# PM.net
KiCad netlist of a schematic drawn in Altium Designer
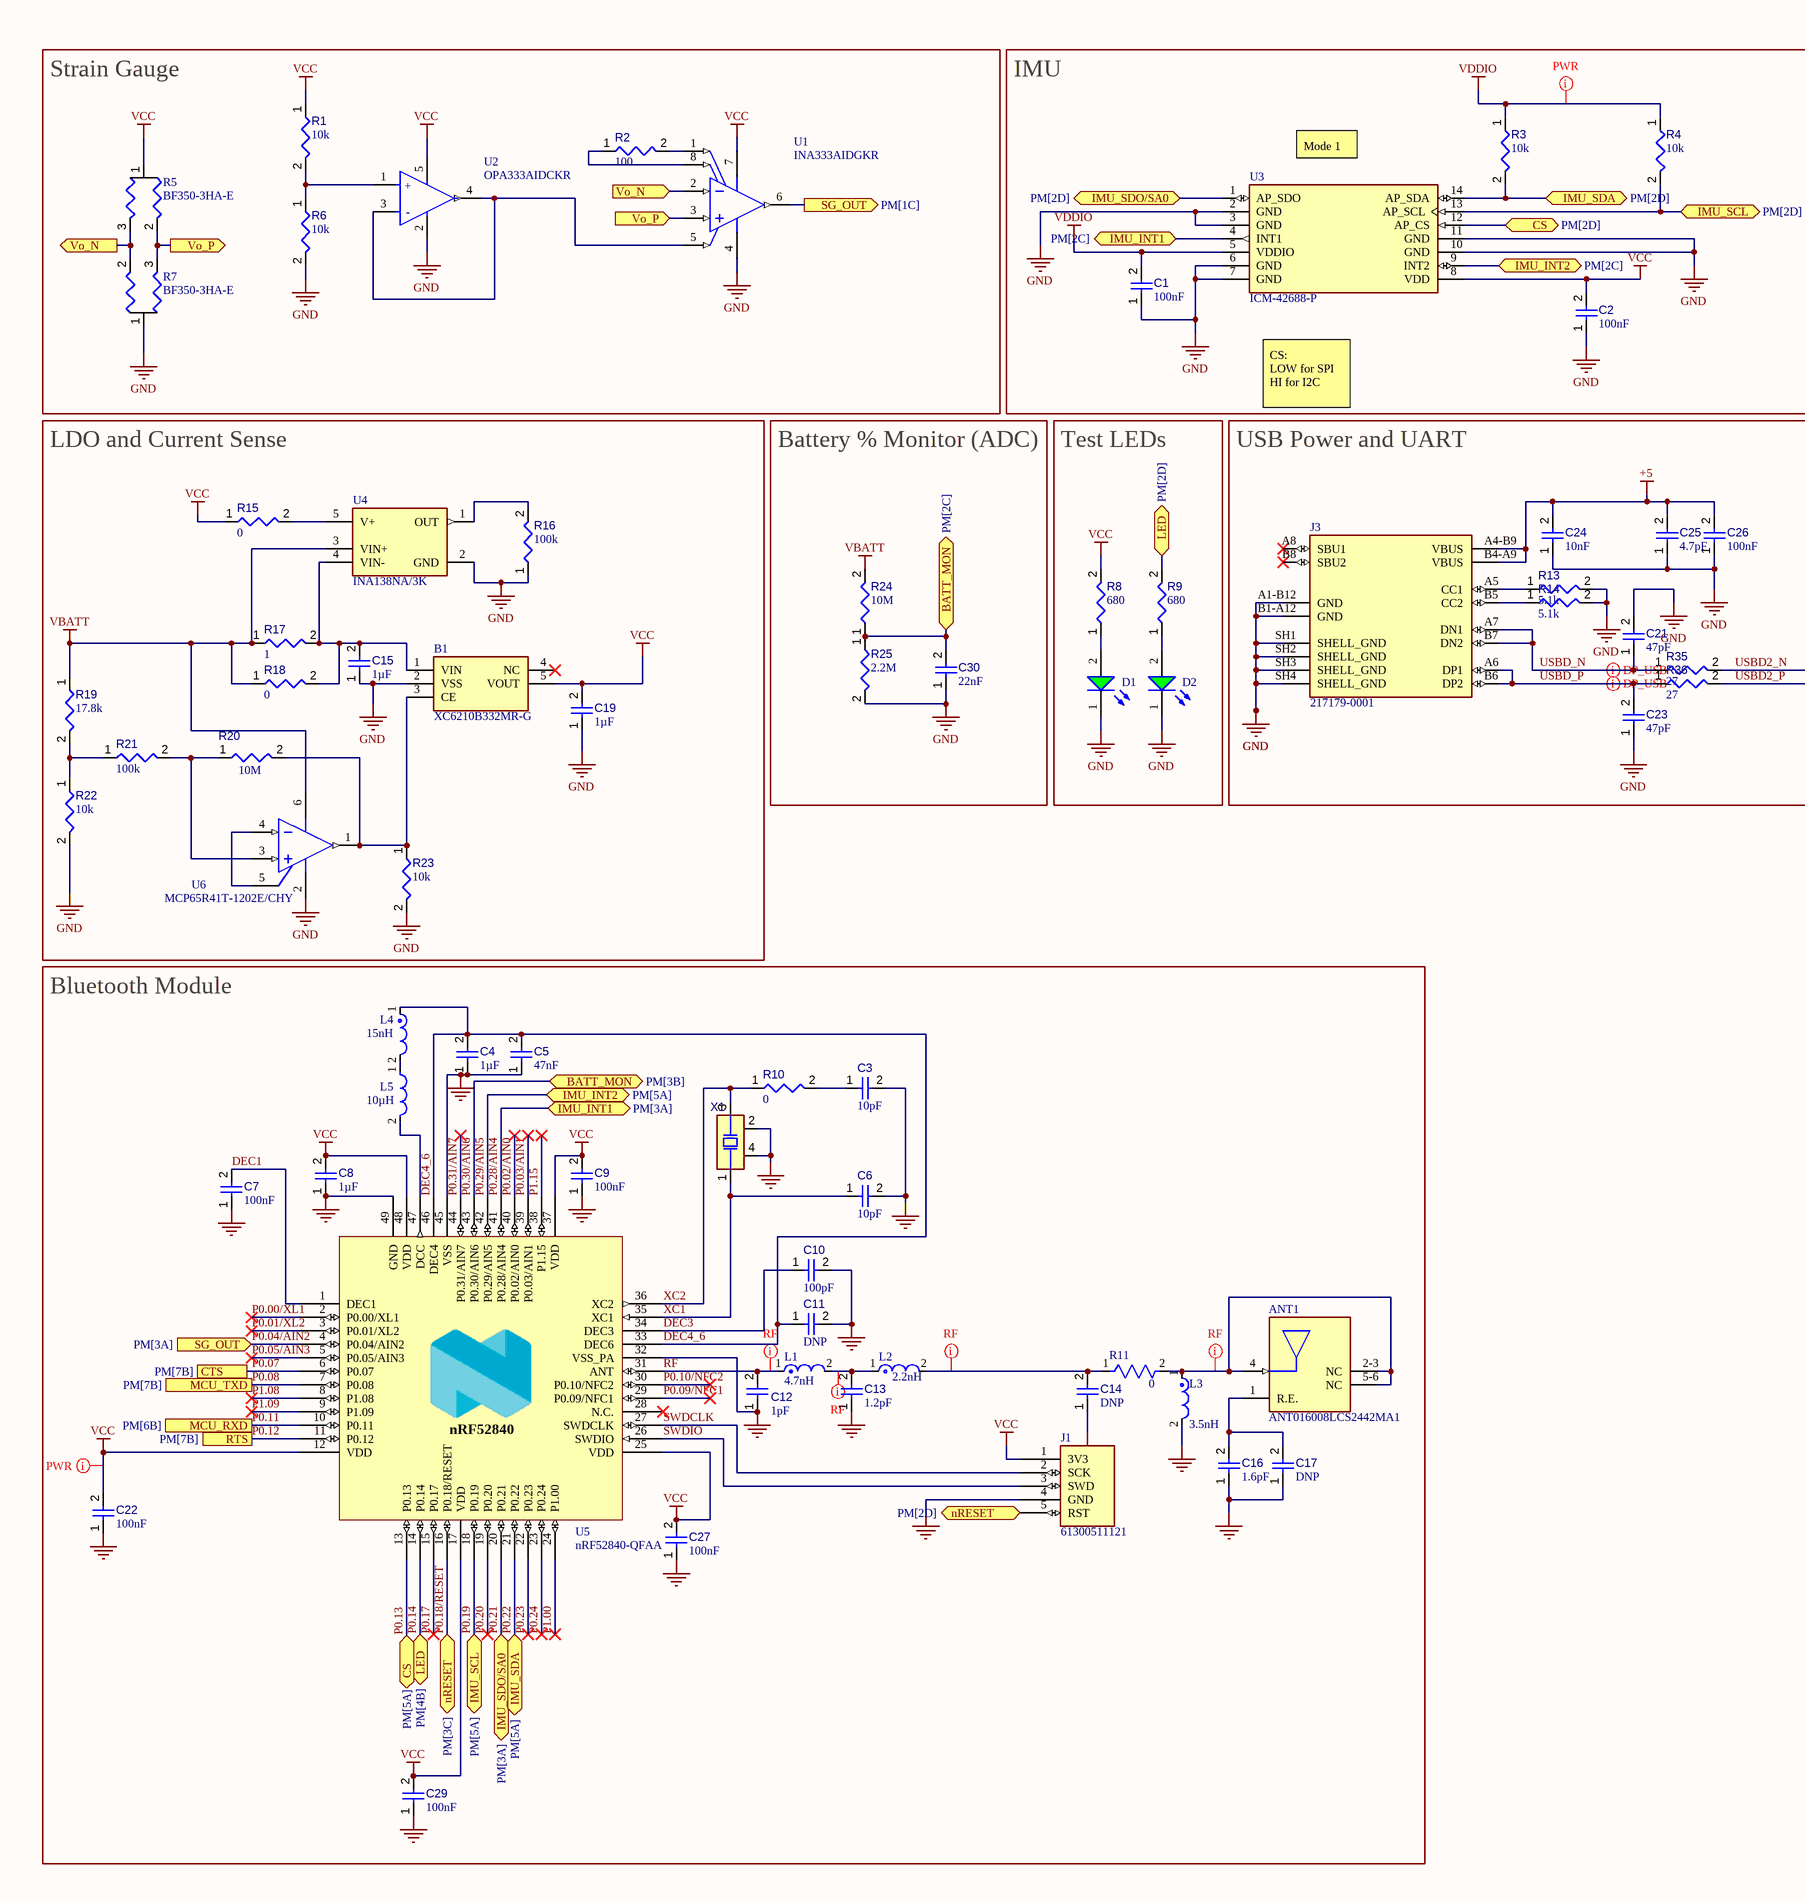
[diagram p0: PM.SchDoc, left]
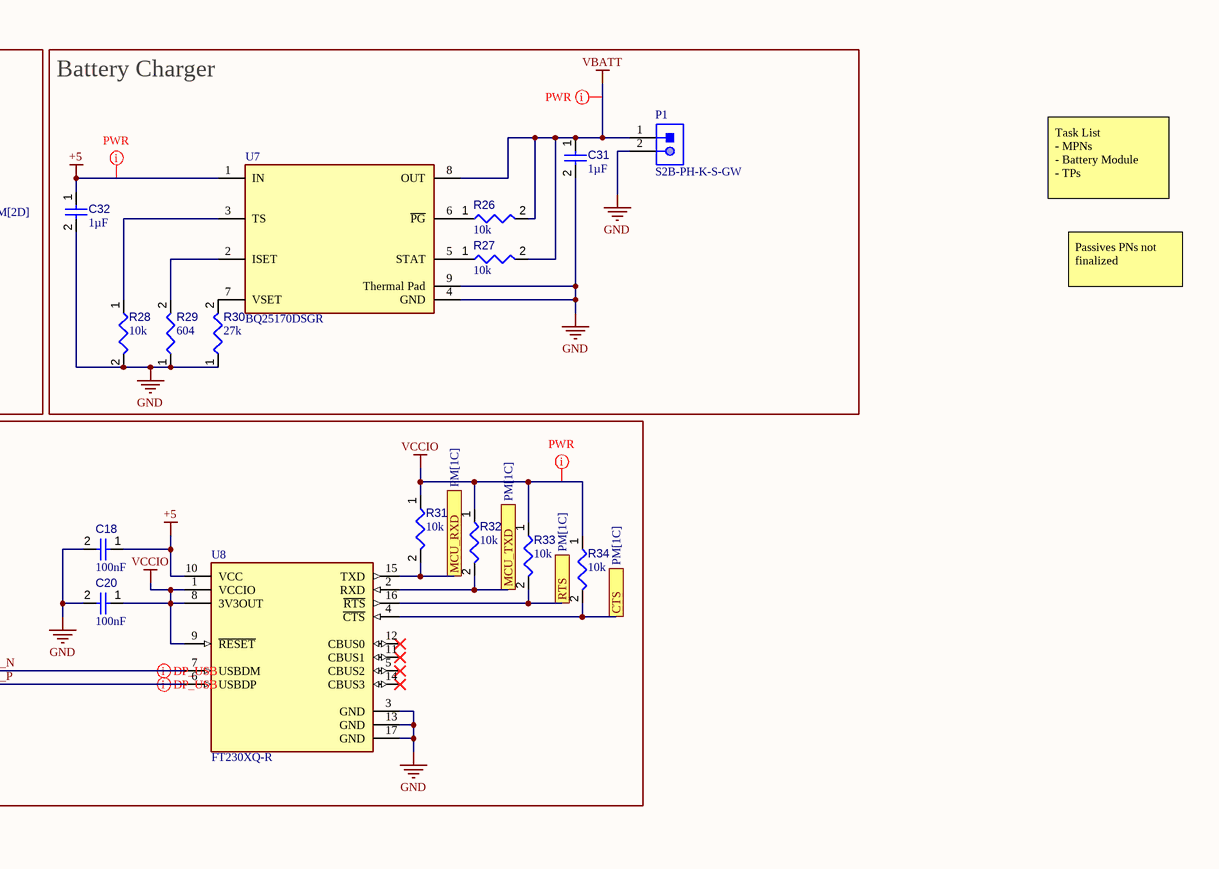
[diagram p1: PM.SchDoc, right]

(export (version "E")
  (design (tool "Eeschema 10.0.6"))
  (components
    (comp (ref "ANT1")
      (value "ANT016008LCS2442MA1")
      (footprint "FP-ANT016-MFG")
      (description "RF/Microwave Antenna, 2400MHz Min, 2484MHz Max")
      (libsource (lib "Capstone") (part "f1d90557cadd8a372defdcae6904fa8"))
    )
    (comp (ref "B1")
      (value "XC6210B332MR-G")
      (footprint "SOT95P280X130-5N")
      (description "LDO Voltage Regulators 700mA High Speed Votage Regulator")
      (fields (field (name "MOUSER PART NUMBER") "865-XC6210B332MR-G"))
      (libsource (lib "Capstone") (part "XC6210B332MR-G"))
    )
    (comp (ref "C1")
      (value "100nF")
      (footprint "FP-GRM15-IPC_B")
      (fields (field (name "Comment") "GRM155R71C104KA88D"))
      (libsource (lib "Capstone") (part "CAP-NP-2"))
    )
    (comp (ref "C2")
      (value "100nF")
      (footprint "FP-GRM15-IPC_B")
      (fields (field (name "Comment") "GRM155R71C104KA88D"))
      (libsource (lib "Capstone") (part "CAP-NP-2"))
    )
    (comp (ref "C3")
      (value "10pF")
      (footprint "FP-GRM155-0_05-IPC_C")
      (fields (field (name "Comment") "GRM1555C1H100FA01D"))
      (libsource (lib "Capstone") (part "CAP-NP-2"))
    )
    (comp (ref "C4")
      (value "1µF")
      (footprint "FP-GRM155-0_05-IPC_C")
      (fields (field (name "Comment") "GRM155R70J105KA12D"))
      (libsource (lib "Capstone") (part "CAP-NP-2"))
    )
    (comp (ref "C5")
      (value "47nF")
      (footprint "CAPC1608X90X35LL10T15")
      (fields (field (name "Comment") "GRM188R71H473KA61D"))
      (libsource (lib "Capstone") (part "CAP-NP-2"))
    )
    (comp (ref "C6")
      (value "10pF")
      (footprint "FP-GRM155-0_05-IPC_C")
      (fields (field (name "Comment") "GRM1555C1H100FA01D"))
      (libsource (lib "Capstone") (part "CAP-NP-2"))
    )
    (comp (ref "C7")
      (value "100nF")
      (footprint "FP-GRM15-IPC_B")
      (fields (field (name "Comment") "GRM155R71C104KA88D"))
      (libsource (lib "Capstone") (part "CAP-NP-2"))
    )
    (comp (ref "C8")
      (value "1µF")
      (footprint "FP-GRM155-0_05-IPC_C")
      (fields (field (name "Comment") "GRM155R70J105KA12D"))
      (libsource (lib "Capstone") (part "CAP-NP-2"))
    )
    (comp (ref "C9")
      (value "100nF")
      (footprint "FP-GRM15-IPC_B")
      (fields (field (name "Comment") "GRM155R71C104KA88D"))
      (libsource (lib "Capstone") (part "CAP-NP-2"))
    )
    (comp (ref "C10")
      (value "100pF")
      (footprint "CAPC1005X55X25LL05T10")
      (fields (field (name "Comment") "GRM1555C1H101JA01D"))
      (libsource (lib "Capstone") (part "CAP-NP-2"))
    )
    (comp (ref "C11")
      (value "DNP")
      (footprint "CAPC0402(1005)33_L")
      (description "Chip Capacitor, 680pF +/-20%, 50V, 0402, Thickness 0.33 mm")
      (fields (field (name "TOLERANCE") "10%") (field (name "Comment") "Capacitor 680pF +/-20% 50V 0402"))
      (libsource (lib "Capstone") (part "CAP-NP-2"))
    )
    (comp (ref "C12")
      (value "GJM0335C1H1R0BB01D")
      (footprint "FP-GJM033-0_03-IPC_B")
      (libsource (lib "Capstone") (part "CAP-NP-2"))
    )
    (comp (ref "C13")
      (value "1.2pF")
      (footprint "FP-GJM033-0_03-IPC_B")
      (fields (field (name "Comment") "GJM0335C1H1R2BB01D"))
      (libsource (lib "Capstone") (part "CAP-NP-2"))
    )
    (comp (ref "C14")
      (value "DNP")
      (footprint "FP-GJM033-0_03-IPC_B")
      (fields (field (name "Comment") "GJM0335C1H1R6BB01D"))
      (libsource (lib "Capstone") (part "CAP-NP-2"))
    )
    (comp (ref "C15")
      (value "1µF")
      (footprint "FP-GRM155-0_05-IPC_C")
      (fields (field (name "Comment") "GRM155R70J105KA12D"))
      (libsource (lib "Capstone") (part "CAP-NP-2"))
    )
    (comp (ref "C16")
      (value "1.6pF")
      (footprint "FP-GJM033-0_03-ANT")
      (fields (field (name "Comment") "GJM0335C1H1R6BB01D"))
      (libsource (lib "Capstone") (part "CAP-NP-2"))
    )
    (comp (ref "C17")
      (value "DNP")
      (footprint "FP-GJM033-0_03-ANT")
      (fields (field (name "Comment") "GJM0335C1H1R6BB01D"))
      (libsource (lib "Capstone") (part "CAP-NP-2"))
    )
    (comp (ref "C18")
      (value "100nF")
      (footprint "FP-GRM15-IPC_B")
      (fields (field (name "Comment") "GRM155R71C104KA88D"))
      (libsource (lib "Capstone") (part "CAP-NP-2"))
    )
    (comp (ref "C19")
      (value "1µF")
      (footprint "FP-GRM155-0_05-IPC_C")
      (fields (field (name "Comment") "GRM155R70J105KA12D"))
      (libsource (lib "Capstone") (part "CAP-NP-2"))
    )
    (comp (ref "C20")
      (value "100nF")
      (footprint "FP-GRM15-IPC_B")
      (fields (field (name "Comment") "GRM155R71C104KA88D"))
      (libsource (lib "Capstone") (part "CAP-NP-2"))
    )
    (comp (ref "C21")
      (value "47pF")
      (footprint "CAPC1005X55X25LL05T10")
      (fields (field (name "Comment") "GRM1555C1H470JA01D"))
      (libsource (lib "Capstone") (part "CAP-NP-2"))
    )
    (comp (ref "C22")
      (value "100nF")
      (footprint "FP-GRM15-IPC_B")
      (fields (field (name "Comment") "GRM155R71C104KA88D"))
      (libsource (lib "Capstone") (part "CAP-NP-2"))
    )
    (comp (ref "C23")
      (value "47pF")
      (footprint "CAPC1005X55X25LL05T10")
      (fields (field (name "Comment") "GRM1555C1H470JA01D"))
      (libsource (lib "Capstone") (part "CAP-NP-2"))
    )
    (comp (ref "C24")
      (value "10nF")
      (footprint "CAPC1005X55X25LL05T10")
      (fields (field (name "Comment") "GRM155R71E103KA01D"))
      (libsource (lib "Capstone") (part "CAP-NP-2"))
    )
    (comp (ref "C25")
      (value "4.7pF")
      (footprint "FP-GRM155-0_05-IPC_B")
      (fields (field (name "Comment") "GRM1555C1H4R7CA01D"))
      (libsource (lib "Capstone") (part "CAP-NP-2"))
    )
    (comp (ref "C26")
      (value "100nF")
      (footprint "FP-GRM15-IPC_B")
      (fields (field (name "Comment") "GRM155R71C104KA88D"))
      (libsource (lib "Capstone") (part "CAP-NP-2"))
    )
    (comp (ref "C27")
      (value "100nF")
      (footprint "FP-GRM15-IPC_B")
      (fields (field (name "Comment") "GRM155R71C104KA88D"))
      (libsource (lib "Capstone") (part "CAP-NP-2"))
    )
    (comp (ref "C29")
      (value "100nF")
      (footprint "FP-GRM15-IPC_B")
      (fields (field (name "Comment") "GRM155R71C104KA88D"))
      (libsource (lib "Capstone") (part "CAP-NP-2"))
    )
    (comp (ref "C30")
      (value "22nF")
      (footprint "FP-GRM155-0_05-MFG")
      (fields (field (name "Comment") "GRM155R71E223JA61D"))
      (libsource (lib "Capstone") (part "CAP-NP-2"))
    )
    (comp (ref "C31")
      (value "1µF")
      (footprint "FP-GRM155-0_05-IPC_C")
      (fields (field (name "Comment") "GRM155R70J105KA12D"))
      (libsource (lib "Capstone") (part "CAP-NP-2"))
    )
    (comp (ref "C32")
      (value "1µF")
      (footprint "FP-GRM155-0_05-IPC_C")
      (fields (field (name "Comment") "GRM155R70J105KA12D"))
      (libsource (lib "Capstone") (part "CAP-NP-2"))
    )
    (comp (ref "D1")
      (value "APHHS1005LCGCK")
      (footprint "LED_APHHS1005LCGCK")
      (description "Green 570nm LED Indication - Discrete 1.9V 0402 (1005 Metric)")
      (fields (field (name "MF") "Kingbright"))
      (libsource (lib "Capstone") (part "LED_Green_2A-1K"))
    )
    (comp (ref "D2")
      (value "APHHS1005LCGCK")
      (footprint "LED_APHHS1005LCGCK")
      (description "Green 570nm LED Indication - Discrete 1.9V 0402 (1005 Metric)")
      (fields (field (name "MF") "Kingbright"))
      (libsource (lib "Capstone") (part "LED_Green_2A-1K"))
    )
    (comp (ref "J1")
      (value "61300511121")
      (footprint "61300511121")
      (libsource (lib "Capstone") (part "DAPLINK_CONN"))
    )
    (comp (ref "J3")
      (value "217179-0001")
      (footprint "FP-2171790001-MFG")
      (description "USB Connector, 16 Contact(s), Female, Right Angle, Surface Mount Terminal, Locking, Receptacle")
      (libsource (lib "Capstone") (part "e7c17a616881a82b79941196b4bec10"))
    )
    (comp (ref "L1")
      (value "4.7nH")
      (footprint "FP-LQP03PN_02-IPC_B")
      (description "Inductor RF Chip Thick Film 0.0047uH 5% 500MHz 10Q-Factor 0.9A 0.14Ohm DCR 0201 T/R")
      (fields (field (name "TOLERANCE") "5%") (field (name "Comment") "LQP03PN4N7J02D"))
      (libsource (lib "Capstone") (part "ae3b6ca10b736fc74204ce580bf9b8e"))
    )
    (comp (ref "L2")
      (value "LQP03TN2N2B02D")
      (footprint "FP-LQP03TG_02-IPC_B")
      (description "General Purpose Inductor, 0.0022uH, 4.545%, 1 Element, SMD, 0201")
      (fields (field (name "TOLERANCE") "4.545%"))
      (libsource (lib "Capstone") (part "4cc4b267dca4c8e51f7102f422741d8"))
    )
    (comp (ref "L3")
      (value "LQP03TN3N5B02D")
      (footprint "FP-LQP03TG_02-IPC_B")
      (description "General Purpose Inductor, 0.0035uH, 2.857%, 1 Element, SMD, 0201")
      (fields (field (name "TOLERANCE") "2.857%"))
      (libsource (lib "Capstone") (part "4cc4b267dca4c8e51f7102f422741d8"))
    )
    (comp (ref "L4")
      (value "15nH")
      (footprint "FP-LQG15HH_02-IPC_B")
      (description "General Purpose Inductor, 0.015uH, 5%, 1 Element, Air-Core, SMD, 0402")
      (fields (field (name "TOLERANCE") "5%") (field (name "Comment") "LQG15HS15NJ02D"))
      (libsource (lib "Capstone") (part "4cc4b267dca4c8e51f7102f422741d8"))
    )
    (comp (ref "L5")
      (value "10µH")
      (footprint "FP-LQM18DN_70-IPC_C")
      (description "General Purpose Inductor, 10uH, 20%, 1 Element, Ferrite-Core, SMD, 0603")
      (fields (field (name "Comment") "LQM18DN100M70L"))
      (libsource (lib "Capstone") (part "725321dda6339637d4d059423bc1c3c"))
    )
    (comp (ref "P1")
      (value "S2B-PH-K-S-GW")
      (footprint "JST-S2B-PH-K-S_V")
      (description "S2B Series 2 Circuit 2 mm Pitch Side Entry Through Hole Shrouded Header")
      (fields (field (name "MANUFACTURER") "Japan Solderless Terminals"))
      (libsource (lib "Capstone") (part "CN-1P-M-R2"))
    )
    (comp (ref "R1")
      (value "10k")
      (footprint "FP-ERA2A-IPC_C")
      (description "Fixed Resistor, Thin Film, 0.063W, 10000ohm, 50V, 0.1% +/-Tol, 25ppm/Cel, Surface Mount, 0402")
      (fields (field (name "POWER") "63mW") (field (name "TOLERANCE") "0.1%"))
      (libsource (lib "Capstone") (part "RES-2"))
    )
    (comp (ref "R2")
      (value "100")
      (footprint "RESC1005X40X25NL05T05")
      (fields
        (field (name "TOLERANCE") "5%")
        (field (name "POWER") "100mW")
        (field (name "Comment") "ERJ-2GEJ101X")
      )
      (libsource (lib "Capstone") (part "RES-2"))
    )
    (comp (ref "R3")
      (value "10k")
      (footprint "FP-ERA2A-IPC_C")
      (description "Fixed Resistor, Thin Film, 0.063W, 10000ohm, 50V, 0.1% +/-Tol, 25ppm/Cel, Surface Mount, 0402")
      (fields (field (name "POWER") "63mW") (field (name "TOLERANCE") "0.1%"))
      (libsource (lib "Capstone") (part "RES-2"))
    )
    (comp (ref "R4")
      (value "10k")
      (footprint "FP-ERA2A-IPC_C")
      (description "Fixed Resistor, Thin Film, 0.063W, 10000ohm, 50V, 0.1% +/-Tol, 25ppm/Cel, Surface Mount, 0402")
      (fields (field (name "POWER") "63mW") (field (name "TOLERANCE") "0.1%"))
      (libsource (lib "Capstone") (part "RES-2"))
    )
    (comp (ref "R5")
      (value "BF350-3HA-E")
      (footprint "BF350-3HA-E-Footprint-1")
      (description "STRAIN GAUGE, SHEAR, 350OHM +/- 3OHM")
      (libsource (lib "Capstone") (part "BF350-3HA-E"))
    )
    (comp (ref "R6")
      (value "10k")
      (footprint "FP-ERA2A-IPC_C")
      (description "Fixed Resistor, Thin Film, 0.063W, 10000ohm, 50V, 0.1% +/-Tol, 25ppm/Cel, Surface Mount, 0402")
      (fields (field (name "POWER") "63mW") (field (name "TOLERANCE") "0.1%"))
      (libsource (lib "Capstone") (part "RES-2"))
    )
    (comp (ref "R7")
      (value "BF350-3HA-E")
      (footprint "BF350-3HA-E-Footprint-1")
      (description "STRAIN GAUGE, SHEAR, 350OHM +/- 3OHM")
      (libsource (lib "Capstone") (part "BF350-3HA-E"))
    )
    (comp (ref "R8")
      (value "680")
      (footprint "FP-ERJ3EK-IPC_C")
      (fields
        (field (name "TOLERANCE") "1%")
        (field (name "POWER") "100mW")
        (field (name "Comment") "ERJ-3EKF6800V")
      )
      (libsource (lib "Capstone") (part "RES-2"))
    )
    (comp (ref "R9")
      (value "680")
      (footprint "FP-ERJ3EK-IPC_C")
      (fields
        (field (name "TOLERANCE") "1%")
        (field (name "POWER") "100mW")
        (field (name "Comment") "ERJ-3EKF6800V")
      )
      (libsource (lib "Capstone") (part "RES-2"))
    )
    (comp (ref "R10")
      (value "0")
      (footprint "RESC0402(1005)_L")
      (description "Jumper 0402")
      (fields (field (name "Comment") "ERJ-2GE0R00X"))
      (libsource (lib "Capstone") (part "RES-2"))
    )
    (comp (ref "R11")
      (value "0")
      (footprint "FP-ERJ1GN-IPC_B")
      (description "Zero Ohm Resistor, Jumper, 0201 [0603 Metric], Thick Film, 50 mW, 500 mA, Surface Mount")
      (fields (field (name "TOLERANCE") "1%") (field (name "Comment") "ERJ-1GN0R00C"))
      (libsource (lib "Capstone") (part "1029c3af85768c4190bb7ad29bc67b5"))
    )
    (comp (ref "R13")
      (value "5.1k")
      (footprint "RESC1005X40X25NL05T05")
      (fields
        (field (name "TOLERANCE") "5%")
        (field (name "POWER") "100mW")
        (field (name "Comment") "ERJ-2GEJ512X")
      )
      (libsource (lib "Capstone") (part "RES-2"))
    )
    (comp (ref "R14")
      (value "5.1k")
      (footprint "RESC1005X40X25NL05T05")
      (fields
        (field (name "TOLERANCE") "5%")
        (field (name "POWER") "100mW")
        (field (name "Comment") "ERJ-2GEJ512X")
      )
      (libsource (lib "Capstone") (part "RES-2"))
    )
    (comp (ref "R15")
      (value "0")
      (footprint "RESC0402(1005)_L")
      (description "Jumper 0402")
      (fields (field (name "Comment") "ERJ-2GE0R00X"))
      (libsource (lib "Capstone") (part "RES-2"))
    )
    (comp (ref "R16")
      (value "100k")
      (footprint "RESC1005X40X25NL05T05")
      (description "Chip Resistor, 100 KOhm, +/- 1%, 0.1 W, -55 to 155 degC, 0402 (1005 Metric)")
      (fields (field (name "POWER") "100mW") (field (name "TOLERANCE") "1%"))
      (libsource (lib "Capstone") (part "RES-2"))
    )
    (comp (ref "R17")
      (value "1")
      (footprint "RESC1005X40X25NL05T10")
      (fields
        (field (name "POWER") "62.5mW")
        (field (name "TOLERANCE") "1%")
        (field (name "Comment") "RC0402FR-071RL")
      )
      (libsource (lib "Capstone") (part "RES-2"))
    )
    (comp (ref "R18")
      (value "0")
      (footprint "RESC0402(1005)_L")
      (description "Jumper 0402")
      (fields (field (name "Comment") "ERJ-2GE0R00X"))
      (libsource (lib "Capstone") (part "RES-2"))
    )
    (comp (ref "R19")
      (value "17.8k")
      (footprint "RESC1005X40X25NL05T10")
      (fields
        (field (name "POWER") "62.5mW")
        (field (name "TOLERANCE") "1%")
        (field (name "Comment") "RC0402FR-0717K8L")
      )
      (libsource (lib "Capstone") (part "RES-2"))
    )
    (comp (ref "R20")
      (value "10M")
      (footprint "RESC1005X40N")
      (description "10 MOhms Â±1% 0.063W, 1/16W Chip Resistor 0402 (1005 Metric) Moisture Resistant Thick Film")
      (fields (field (name "MP") "RC0402FR-0710ML") (field (name "MF") "Yageo"))
      (libsource (lib "Capstone") (part "RES-2"))
    )
    (comp (ref "R21")
      (value "100k")
      (footprint "RESC1005X40X25NL05T05")
      (description "Chip Resistor, 100 KOhm, +/- 1%, 0.1 W, -55 to 155 degC, 0402 (1005 Metric)")
      (fields (field (name "POWER") "100mW") (field (name "TOLERANCE") "1%"))
      (libsource (lib "Capstone") (part "RES-2"))
    )
    (comp (ref "R22")
      (value "10k")
      (footprint "FP-ERA2A-IPC_C")
      (description "Fixed Resistor, Thin Film, 0.063W, 10000ohm, 50V, 0.1% +/-Tol, 25ppm/Cel, Surface Mount, 0402")
      (fields (field (name "POWER") "63mW") (field (name "TOLERANCE") "0.1%"))
      (libsource (lib "Capstone") (part "RES-2"))
    )
    (comp (ref "R23")
      (value "10k")
      (footprint "FP-ERA2A-IPC_C")
      (description "Fixed Resistor, Thin Film, 0.063W, 10000ohm, 50V, 0.1% +/-Tol, 25ppm/Cel, Surface Mount, 0402")
      (fields (field (name "POWER") "63mW") (field (name "TOLERANCE") "0.1%"))
      (libsource (lib "Capstone") (part "RES-2"))
    )
    (comp (ref "R24")
      (value "10M")
      (footprint "RESC1005X40N")
      (description "10 MOhms Â±1% 0.063W, 1/16W Chip Resistor 0402 (1005 Metric) Moisture Resistant Thick Film")
      (fields (field (name "MP") "RC0402FR-0710ML") (field (name "MF") "Yageo"))
      (libsource (lib "Capstone") (part "RES-2"))
    )
    (comp (ref "R25")
      (value "2.2M")
      (footprint "FP-CRCW0402-e3-IPC_B")
      (fields
        (field (name "POWER") "63mW")
        (field (name "TOLERANCE") "1%")
        (field (name "Comment") "CRCW04022M20FKED")
      )
      (libsource (lib "Capstone") (part "RES-2"))
    )
    (comp (ref "R26")
      (value "10k")
      (footprint "FP-ERA2A-IPC_C")
      (description "Fixed Resistor, Thin Film, 0.063W, 10000ohm, 50V, 0.1% +/-Tol, 25ppm/Cel, Surface Mount, 0402")
      (fields (field (name "POWER") "63mW") (field (name "TOLERANCE") "0.1%"))
      (libsource (lib "Capstone") (part "RES-2"))
    )
    (comp (ref "R27")
      (value "10k")
      (footprint "FP-ERA2A-IPC_C")
      (description "Fixed Resistor, Thin Film, 0.063W, 10000ohm, 50V, 0.1% +/-Tol, 25ppm/Cel, Surface Mount, 0402")
      (fields (field (name "POWER") "63mW") (field (name "TOLERANCE") "0.1%"))
      (libsource (lib "Capstone") (part "RES-2"))
    )
    (comp (ref "R28")
      (value "10k")
      (footprint "FP-ERA2A-IPC_C")
      (description "Fixed Resistor, Thin Film, 0.063W, 10000ohm, 50V, 0.1% +/-Tol, 25ppm/Cel, Surface Mount, 0402")
      (fields (field (name "POWER") "63mW") (field (name "TOLERANCE") "0.1%"))
      (libsource (lib "Capstone") (part "RES-2"))
    )
    (comp (ref "R29")
      (value "604")
      (footprint "RESC1005X40X25NL05T05")
      (fields
        (field (name "TOLERANCE") "1%")
        (field (name "POWER") "100mW")
        (field (name "Comment") "ERJ-2RKF6040X")
      )
      (libsource (lib "Capstone") (part "RES-2"))
    )
    (comp (ref "R30")
      (value "27k")
      (footprint "RESC1005X40X25NL05T05")
      (fields
        (field (name "POWER") "100mW")
        (field (name "TOLERANCE") "1%")
        (field (name "Comment") "ERJ-2RKF2702X")
      )
      (libsource (lib "Capstone") (part "RES-2"))
    )
    (comp (ref "R31")
      (value "10k")
      (footprint "FP-ERA2A-IPC_C")
      (description "Fixed Resistor, Thin Film, 0.063W, 10000ohm, 50V, 0.1% +/-Tol, 25ppm/Cel, Surface Mount, 0402")
      (fields (field (name "POWER") "63mW") (field (name "TOLERANCE") "0.1%"))
      (libsource (lib "Capstone") (part "RES-2"))
    )
    (comp (ref "R32")
      (value "10k")
      (footprint "FP-ERA2A-IPC_C")
      (description "Fixed Resistor, Thin Film, 0.063W, 10000ohm, 50V, 0.1% +/-Tol, 25ppm/Cel, Surface Mount, 0402")
      (fields (field (name "POWER") "63mW") (field (name "TOLERANCE") "0.1%"))
      (libsource (lib "Capstone") (part "RES-2"))
    )
    (comp (ref "R33")
      (value "10k")
      (footprint "FP-ERA2A-IPC_C")
      (description "Fixed Resistor, Thin Film, 0.063W, 10000ohm, 50V, 0.1% +/-Tol, 25ppm/Cel, Surface Mount, 0402")
      (fields (field (name "POWER") "63mW") (field (name "TOLERANCE") "0.1%"))
      (libsource (lib "Capstone") (part "RES-2"))
    )
    (comp (ref "R34")
      (value "10k")
      (footprint "FP-ERA2A-IPC_C")
      (description "Fixed Resistor, Thin Film, 0.063W, 10000ohm, 50V, 0.1% +/-Tol, 25ppm/Cel, Surface Mount, 0402")
      (fields (field (name "POWER") "63mW") (field (name "TOLERANCE") "0.1%"))
      (libsource (lib "Capstone") (part "RES-2"))
    )
    (comp (ref "R35")
      (value "27")
      (footprint "RESC1005X40X25ML05T05")
      (fields
        (field (name "POWER") "100mW")
        (field (name "TOLERANCE") "5%")
        (field (name "Comment") "ERJ-2GEJ270X")
      )
      (libsource (lib "Capstone") (part "RES-2"))
    )
    (comp (ref "R36")
      (value "27")
      (footprint "RESC1005X40X25ML05T05")
      (fields
        (field (name "POWER") "100mW")
        (field (name "TOLERANCE") "5%")
        (field (name "Comment") "ERJ-2GEJ270X")
      )
      (libsource (lib "Capstone") (part "RES-2"))
    )
    (comp (ref "U1")
      (value "INA333AIDGKR")
      (footprint "DGK0008A_M")
      (description "Instrumentation Amplifier, 1 Func, 25uV Offset-Max, 0.15MHz Band Width, PDSO8")
      (libsource (lib "Capstone") (part "TI-INAXXXXXX8"))
    )
    (comp (ref "U2")
      (value "OPA333AIDCKR")
      (footprint "FP-DCK0005A-MFG")
      (description "Operational Amplifier, 1 Func, 10uV Offset-Max, CMOS, PDSO5")
      (fields (field (name "POWER") "0W"))
      (libsource (lib "Capstone") (part "000f5c41575af8b8d083a31a5be8140"))
    )
    (comp (ref "U3")
      (value "ICM-42688-P")
      (footprint "PQFN50P300X250X97-14N")
      (description "Accelerometer, Gyroscope, 6 Axis Sensor Output")
      (libsource (lib "Capstone") (part "ICM-42688-P"))
    )
    (comp (ref "U4")
      (value "INA138NA/3K")
      (footprint "FP-DBV0005A-IPC_C")
      (description "Operational Amplifier, 1 Func, PDSO5")
      (libsource (lib "Capstone") (part "4c3a0e1664c42986472e642d50d35bc"))
    )
    (comp (ref "U5")
      (value "nRF52840-QFAA")
      (footprint "QFN40P600X600X90-48N")
      (description "Multi-protocol Bluetooth Low Energy, IEEE 802.15.4, ANT and 2.4GHz proprietary system-on-chip")
      (libsource (lib "Capstone") (part "nRF52840-QFAA"))
    )
    (comp (ref "U6")
      (value "MCP65R41T-1202E/CHY")
      (footprint "SOT-23-CHY6_M")
      (description "Comparator, 1 Func, 10000uV Offset-Max, 4000ns Response Time, CMOS, PDSO6")
      (libsource (lib "Capstone") (part "LO-COMP-MCP65R41-SOT6"))
    )
    (comp (ref "U7")
      (value "BQ25170DSGR")
      (footprint "FP-DSG0008A-IPC_B")
      (description "Power Supply Support Circuit, Adjustable, 1 Channel, PDSO8")
      (libsource (lib "Capstone") (part "8a2467e5c458e831b7d8dd803ec95f1"))
    )
    (comp (ref "U8")
      (value "FT230XQ-R")
      (footprint "FP-QFN-16-IPC_A")
      (description "Microprocessor Circuit, CMOS, PQCC16")
      (libsource (lib "Capstone") (part "29d2eb9587eff32afae5da052de4085"))
    )
    (comp (ref "X1")
      (value "FA-128 32.0000MF20X-K5")
      (footprint "BT-XTAL_2016")
      (description "32 MHz ±10ppm Crystal 10pF 60 Ohms 4-SMD, No Lead")
      (libsource (lib "Capstone") (part "CMP-00014-7"))
    )
  )
  (nets
    (net (code "1") (name "+5") (class "Default")
      (node (ref "C18") (pin "1") (pinfunction "1_1") (pintype "passive"))
      (node (ref "C24") (pin "2") (pinfunction "2_2") (pintype "passive"))
      (node (ref "C25") (pin "2") (pinfunction "2_2") (pintype "passive"))
      (node (ref "C26") (pin "2") (pinfunction "2_2") (pintype "passive"))
      (node (ref "C32") (pin "1") (pinfunction "1_1") (pintype "passive"))
      (node (ref "J3") (pin "A4-B9") (pinfunction "VBUS_A4-B9") (pintype "power_in"))
      (node (ref "J3") (pin "B4-A9") (pinfunction "VBUS_B4-A9") (pintype "power_in"))
      (node (ref "U7") (pin "1") (pinfunction "IN_1") (pintype "power_in"))
      (node (ref "U8") (pin "10") (pinfunction "VCC_10") (pintype "power_in"))
    )
    (net (code "2") (name "/DEC1") (class "Default")
      (node (ref "C7") (pin "2") (pinfunction "2_2") (pintype "passive"))
      (node (ref "U5") (pin "1") (pinfunction "DEC1_1") (pintype "power_in"))
    )
    (net (code "3") (name "/DEC3") (class "Default")
      (node (ref "C10") (pin "1") (pinfunction "1_1") (pintype "passive"))
      (node (ref "U5") (pin "34") (pinfunction "DEC3_34") (pintype "power_in"))
    )
    (net (code "4") (name "/DEC4_6") (class "Default")
      (node (ref "C11") (pin "1") (pinfunction "1_1") (pintype "passive"))
      (node (ref "C4") (pin "2") (pinfunction "2_2") (pintype "passive"))
      (node (ref "C5") (pin "2") (pinfunction "2_2") (pintype "passive"))
      (node (ref "L4") (pin "1") (pinfunction "1_1") (pintype "passive"))
      (node (ref "U5") (pin "33") (pinfunction "DEC6_33") (pintype "power_in"))
      (node (ref "U5") (pin "46") (pinfunction "DEC4_46") (pintype "power_in"))
    )
    (net (code "5") (name "/P0.00{slash}XL1") (class "Default")
      (node (ref "U5") (pin "2") (pinfunction "P0.00/XL1_2") (pintype "bidirectional+no_connect"))
    )
    (net (code "6") (name "/P0.01{slash}XL2") (class "Default")
      (node (ref "U5") (pin "3") (pinfunction "P0.01/XL2_3") (pintype "bidirectional+no_connect"))
    )
    (net (code "7") (name "/P0.02{slash}AIN0") (class "Default")
      (node (ref "U5") (pin "40") (pinfunction "P0.02/AIN0_40") (pintype "bidirectional+no_connect"))
    )
    (net (code "8") (name "/P0.03{slash}AIN1") (class "Default")
      (node (ref "U5") (pin "39") (pinfunction "P0.03/AIN1_39") (pintype "bidirectional+no_connect"))
    )
    (net (code "9") (name "/P0.04{slash}AIN2") (class "Default")
      (node (ref "U1") (pin "6") (pinfunction "VOUT_6") (pintype "output"))
      (node (ref "U5") (pin "4") (pinfunction "P0.04/AIN2_4") (pintype "bidirectional"))
    )
    (net (code "10") (name "/P0.05{slash}AIN3") (class "Default")
      (node (ref "U5") (pin "5") (pinfunction "P0.05/AIN3_5") (pintype "bidirectional+no_connect"))
    )
    (net (code "11") (name "/P0.07") (class "Default")
      (node (ref "R34") (pin "2") (pinfunction "2_2") (pintype "passive"))
      (node (ref "U5") (pin "6") (pinfunction "P0.07_6") (pintype "bidirectional"))
      (node (ref "U8") (pin "4") (pinfunction "~{CTS}_4") (pintype "input"))
    )
    (net (code "12") (name "/P0.08") (class "Default")
      (node (ref "R32") (pin "2") (pinfunction "2_2") (pintype "passive"))
      (node (ref "U5") (pin "7") (pinfunction "P0.08_7") (pintype "bidirectional"))
      (node (ref "U8") (pin "2") (pinfunction "RXD_2") (pintype "input"))
    )
    (net (code "13") (name "/P0.09{slash}NFC1") (class "Default")
      (node (ref "U5") (pin "29") (pinfunction "P0.09/NFC1_29") (pintype "bidirectional+no_connect"))
    )
    (net (code "14") (name "/P0.10{slash}NFC2") (class "Default")
      (node (ref "U5") (pin "30") (pinfunction "P0.10/NFC2_30") (pintype "bidirectional+no_connect"))
    )
    (net (code "15") (name "/P0.11") (class "Default")
      (node (ref "R31") (pin "2") (pinfunction "2_2") (pintype "passive"))
      (node (ref "U5") (pin "10") (pinfunction "P0.11_10") (pintype "bidirectional"))
      (node (ref "U8") (pin "15") (pinfunction "TXD_15") (pintype "output"))
    )
    (net (code "16") (name "/P0.12") (class "Default")
      (node (ref "R33") (pin "2") (pinfunction "2_2") (pintype "passive"))
      (node (ref "U5") (pin "11") (pinfunction "P0.12_11") (pintype "bidirectional"))
      (node (ref "U8") (pin "16") (pinfunction "~{RTS}_16") (pintype "output"))
    )
    (net (code "17") (name "/P0.13") (class "Default")
      (node (ref "U3") (pin "12") (pinfunction "AP_CS_12") (pintype "input"))
      (node (ref "U5") (pin "13") (pinfunction "P0.13_13") (pintype "bidirectional"))
    )
    (net (code "18") (name "/P0.14") (class "Default")
      (node (ref "R9") (pin "2") (pinfunction "2_2") (pintype "passive"))
      (node (ref "U5") (pin "14") (pinfunction "P0.14_14") (pintype "bidirectional"))
    )
    (net (code "19") (name "/P0.17") (class "Default")
      (node (ref "U5") (pin "15") (pinfunction "P0.17_15") (pintype "bidirectional+no_connect"))
    )
    (net (code "20") (name "/P0.18{slash}RESET") (class "Default")
      (node (ref "J1") (pin "5") (pinfunction "RST_5") (pintype "bidirectional"))
      (node (ref "U5") (pin "16") (pinfunction "P0.18/RESET_16") (pintype "bidirectional"))
    )
    (net (code "21") (name "/P0.19") (class "Default")
      (node (ref "R4") (pin "2") (pinfunction "2_2") (pintype "passive"))
      (node (ref "U3") (pin "13") (pinfunction "AP_SCL_13") (pintype "input"))
      (node (ref "U5") (pin "18") (pinfunction "P0.19_18") (pintype "bidirectional"))
    )
    (net (code "22") (name "/P0.20") (class "Default")
      (node (ref "U5") (pin "19") (pinfunction "P0.20_19") (pintype "bidirectional+no_connect"))
    )
    (net (code "23") (name "/P0.21") (class "Default")
      (node (ref "U3") (pin "1") (pinfunction "AP_SDO_1") (pintype "bidirectional"))
      (node (ref "U5") (pin "20") (pinfunction "P0.21_20") (pintype "bidirectional"))
    )
    (net (code "24") (name "/P0.22") (class "Default")
      (node (ref "R3") (pin "2") (pinfunction "2_2") (pintype "passive"))
      (node (ref "U3") (pin "14") (pinfunction "AP_SDA_14") (pintype "bidirectional"))
      (node (ref "U5") (pin "21") (pinfunction "P0.22_21") (pintype "bidirectional"))
    )
    (net (code "25") (name "/P0.23") (class "Default")
      (node (ref "U5") (pin "22") (pinfunction "P0.23_22") (pintype "bidirectional+no_connect"))
    )
    (net (code "26") (name "/P0.24") (class "Default")
      (node (ref "U5") (pin "23") (pinfunction "P0.24_23") (pintype "bidirectional+no_connect"))
    )
    (net (code "27") (name "/P0.28{slash}AIN4") (class "Default")
      (node (ref "U3") (pin "4") (pinfunction "INT1_4") (pintype "output"))
      (node (ref "U5") (pin "41") (pinfunction "P0.28/AIN4_41") (pintype "bidirectional"))
    )
    (net (code "28") (name "/P0.29{slash}AIN5") (class "Default")
      (node (ref "U3") (pin "9") (pinfunction "INT2_9") (pintype "bidirectional"))
      (node (ref "U5") (pin "42") (pinfunction "P0.29/AIN5_42") (pintype "bidirectional"))
    )
    (net (code "29") (name "/P0.30{slash}AIN6") (class "Default")
      (node (ref "C30") (pin "2") (pinfunction "2_2") (pintype "passive"))
      (node (ref "R24") (pin "1") (pinfunction "1_1") (pintype "passive"))
      (node (ref "R25") (pin "1") (pinfunction "1_1") (pintype "passive"))
      (node (ref "U5") (pin "43") (pinfunction "P0.30/AIN6_43") (pintype "bidirectional"))
    )
    (net (code "30") (name "/P0.31{slash}AIN7") (class "Default")
      (node (ref "U5") (pin "44") (pinfunction "P0.31/AIN7_44") (pintype "bidirectional+no_connect"))
    )
    (net (code "31") (name "/P1.00") (class "Default")
      (node (ref "U5") (pin "24") (pinfunction "P1.00_24") (pintype "bidirectional+no_connect"))
    )
    (net (code "32") (name "/P1.08") (class "Default")
      (node (ref "U5") (pin "8") (pinfunction "P1.08_8") (pintype "bidirectional+no_connect"))
    )
    (net (code "33") (name "/P1.09") (class "Default")
      (node (ref "U5") (pin "9") (pinfunction "P1.09_9") (pintype "bidirectional+no_connect"))
    )
    (net (code "34") (name "/P1.15") (class "Default")
      (node (ref "U5") (pin "38") (pinfunction "P1.15_38") (pintype "bidirectional+no_connect"))
    )
    (net (code "35") (name "/RF") (class "Default")
      (node (ref "C12") (pin "2") (pinfunction "2_2") (pintype "passive"))
      (node (ref "L1") (pin "1") (pinfunction "1_1") (pintype "passive"))
      (node (ref "U5") (pin "31") (pinfunction "ANT_31") (pintype "bidirectional"))
    )
    (net (code "36") (name "/SWDCLK") (class "Default")
      (node (ref "J1") (pin "2") (pinfunction "SCK_2") (pintype "bidirectional"))
      (node (ref "U5") (pin "27") (pinfunction "SWDCLK_27") (pintype "bidirectional"))
    )
    (net (code "37") (name "/SWDIO") (class "Default")
      (node (ref "J1") (pin "3") (pinfunction "SWD_3") (pintype "bidirectional"))
      (node (ref "U5") (pin "26") (pinfunction "SWDIO_26") (pintype "input"))
    )
    (net (code "38") (name "/USBD2_N") (class "Default")
      (node (ref "R35") (pin "2") (pinfunction "2_2") (pintype "passive"))
      (node (ref "U8") (pin "7") (pinfunction "USBDM_7") (pintype "input"))
    )
    (net (code "39") (name "/USBD2_P") (class "Default")
      (node (ref "R36") (pin "2") (pinfunction "2_2") (pintype "passive"))
      (node (ref "U8") (pin "6") (pinfunction "USBDP_6") (pintype "input"))
    )
    (net (code "40") (name "/USBD_N") (class "Default")
      (node (ref "C21") (pin "1") (pinfunction "1_1") (pintype "passive"))
      (node (ref "J3") (pin "A7") (pinfunction "DN1_A7") (pintype "bidirectional"))
      (node (ref "J3") (pin "B7") (pinfunction "DN2_B7") (pintype "bidirectional"))
      (node (ref "R35") (pin "1") (pinfunction "1_1") (pintype "passive"))
    )
    (net (code "41") (name "/USBD_P") (class "Default")
      (node (ref "C23") (pin "2") (pinfunction "2_2") (pintype "passive"))
      (node (ref "J3") (pin "A6") (pinfunction "DP1_A6") (pintype "bidirectional"))
      (node (ref "J3") (pin "B6") (pinfunction "DP2_B6") (pintype "bidirectional"))
      (node (ref "R36") (pin "1") (pinfunction "1_1") (pintype "passive"))
    )
    (net (code "42") (name "/Vo_N") (class "Default")
      (node (ref "R5") (pin "3") (pinfunction "3_3") (pintype "passive"))
      (node (ref "R7") (pin "2") (pinfunction "2_2") (pintype "passive"))
      (node (ref "U1") (pin "2") (pinfunction "VIN-_2") (pintype "input"))
    )
    (net (code "43") (name "/Vo_P") (class "Default")
      (node (ref "R5") (pin "2") (pinfunction "2_2") (pintype "passive"))
      (node (ref "R7") (pin "3") (pinfunction "3_3") (pintype "passive"))
      (node (ref "U1") (pin "3") (pinfunction "VIN+_3") (pintype "input"))
    )
    (net (code "44") (name "/XC1") (class "Default")
      (node (ref "C6") (pin "1") (pinfunction "1_1") (pintype "passive"))
      (node (ref "U5") (pin "35") (pinfunction "XC1_35") (pintype "input"))
      (node (ref "X1") (pin "1") (pinfunction "X1_1") (pintype "passive"))
    )
    (net (code "45") (name "/XC2") (class "Default")
      (node (ref "R10") (pin "1") (pinfunction "1_1") (pintype "passive"))
      (node (ref "U5") (pin "36") (pinfunction "XC2_36") (pintype "output"))
      (node (ref "X1") (pin "3") (pinfunction "X2_3") (pintype "passive"))
    )
    (net (code "46") (name "GND") (class "Default")
      (node (ref "B1") (pin "2") (pinfunction "VSS_2") (pintype "passive"))
      (node (ref "C1") (pin "1") (pinfunction "1_1") (pintype "passive"))
      (node (ref "C10") (pin "2") (pinfunction "2_2") (pintype "passive"))
      (node (ref "C11") (pin "2") (pinfunction "2_2") (pintype "passive"))
      (node (ref "C12") (pin "1") (pinfunction "1_1") (pintype "passive"))
      (node (ref "C13") (pin "1") (pinfunction "1_1") (pintype "passive"))
      (node (ref "C14") (pin "1") (pinfunction "1_1") (pintype "passive"))
      (node (ref "C15") (pin "1") (pinfunction "1_1") (pintype "passive"))
      (node (ref "C16") (pin "1") (pinfunction "1_1") (pintype "passive"))
      (node (ref "C17") (pin "1") (pinfunction "1_1") (pintype "passive"))
      (node (ref "C18") (pin "2") (pinfunction "2_2") (pintype "passive"))
      (node (ref "C19") (pin "1") (pinfunction "1_1") (pintype "passive"))
      (node (ref "C2") (pin "1") (pinfunction "1_1") (pintype "passive"))
      (node (ref "C20") (pin "2") (pinfunction "2_2") (pintype "passive"))
      (node (ref "C21") (pin "2") (pinfunction "2_2") (pintype "passive"))
      (node (ref "C22") (pin "1") (pinfunction "1_1") (pintype "passive"))
      (node (ref "C23") (pin "1") (pinfunction "1_1") (pintype "passive"))
      (node (ref "C24") (pin "1") (pinfunction "1_1") (pintype "passive"))
      (node (ref "C25") (pin "1") (pinfunction "1_1") (pintype "passive"))
      (node (ref "C26") (pin "1") (pinfunction "1_1") (pintype "passive"))
      (node (ref "C27") (pin "1") (pinfunction "1_1") (pintype "passive"))
      (node (ref "C29") (pin "1") (pinfunction "1_1") (pintype "passive"))
      (node (ref "C3") (pin "2") (pinfunction "2_2") (pintype "passive"))
      (node (ref "C30") (pin "1") (pinfunction "1_1") (pintype "passive"))
      (node (ref "C31") (pin "2") (pinfunction "2_2") (pintype "passive"))
      (node (ref "C32") (pin "2") (pinfunction "2_2") (pintype "passive"))
      (node (ref "C4") (pin "1") (pinfunction "1_1") (pintype "passive"))
      (node (ref "C5") (pin "1") (pinfunction "1_1") (pintype "passive"))
      (node (ref "C6") (pin "2") (pinfunction "2_2") (pintype "passive"))
      (node (ref "C7") (pin "1") (pinfunction "1_1") (pintype "passive"))
      (node (ref "C8") (pin "1") (pinfunction "1_1") (pintype "passive"))
      (node (ref "C9") (pin "1") (pinfunction "1_1") (pintype "passive"))
      (node (ref "D1") (pin "1") (pinfunction "K_1") (pintype "passive"))
      (node (ref "D2") (pin "1") (pinfunction "K_1") (pintype "passive"))
      (node (ref "J1") (pin "4") (pinfunction "GND_4") (pintype "power_in"))
      (node (ref "J3") (pin "A1-B12") (pinfunction "GND_A1-B12") (pintype "power_in"))
      (node (ref "J3") (pin "B1-A12") (pinfunction "GND_B1-A12") (pintype "power_in"))
      (node (ref "J3") (pin "SH1") (pinfunction "SHELL_GND_SH1") (pintype "power_in"))
      (node (ref "J3") (pin "SH2") (pinfunction "SHELL_GND_SH2") (pintype "power_in"))
      (node (ref "J3") (pin "SH3") (pinfunction "SHELL_GND_SH3") (pintype "power_in"))
      (node (ref "J3") (pin "SH4") (pinfunction "SHELL_GND_SH4") (pintype "power_in"))
      (node (ref "L3") (pin "2") (pinfunction "2_2") (pintype "passive"))
      (node (ref "P1") (pin "2") (pinfunction "2_2") (pintype "passive"))
      (node (ref "R13") (pin "2") (pinfunction "2_2") (pintype "passive"))
      (node (ref "R14") (pin "2") (pinfunction "2_2") (pintype "passive"))
      (node (ref "R16") (pin "1") (pinfunction "1_1") (pintype "passive"))
      (node (ref "R22") (pin "2") (pinfunction "2_2") (pintype "passive"))
      (node (ref "R23") (pin "2") (pinfunction "2_2") (pintype "passive"))
      (node (ref "R25") (pin "2") (pinfunction "2_2") (pintype "passive"))
      (node (ref "R28") (pin "2") (pinfunction "2_2") (pintype "passive"))
      (node (ref "R29") (pin "1") (pinfunction "1_1") (pintype "passive"))
      (node (ref "R30") (pin "1") (pinfunction "1_1") (pintype "passive"))
      (node (ref "R6") (pin "2") (pinfunction "2_2") (pintype "passive"))
      (node (ref "R7") (pin "1") (pinfunction "1_1") (pintype "passive"))
      (node (ref "U1") (pin "4") (pinfunction "V-_4") (pintype "power_in"))
      (node (ref "U2") (pin "2") (pinfunction "V-_2") (pintype "power_in"))
      (node (ref "U3") (pin "10") (pinfunction "GND_10") (pintype "power_in"))
      (node (ref "U3") (pin "11") (pinfunction "GND_11") (pintype "power_in"))
      (node (ref "U3") (pin "2") (pinfunction "GND_2") (pintype "power_in"))
      (node (ref "U3") (pin "3") (pinfunction "GND_3") (pintype "power_in"))
      (node (ref "U3") (pin "6") (pinfunction "GND_6") (pintype "power_in"))
      (node (ref "U3") (pin "7") (pinfunction "GND_7") (pintype "power_in"))
      (node (ref "U4") (pin "2") (pinfunction "GND_2") (pintype "power_in"))
      (node (ref "U5") (pin "32") (pinfunction "VSS_PA_32") (pintype "power_in"))
      (node (ref "U5") (pin "45") (pinfunction "VSS_45") (pintype "power_in"))
      (node (ref "U5") (pin "49") (pinfunction "GND_49") (pintype "power_in"))
      (node (ref "U6") (pin "2") (pinfunction "VSS_2") (pintype "power_in"))
      (node (ref "U7") (pin "4") (pinfunction "GND_4") (pintype "power_in"))
      (node (ref "U7") (pin "9") (pinfunction "Thermal_Pad_9") (pintype "power_in"))
      (node (ref "U8") (pin "13") (pinfunction "GND_13") (pintype "power_in"))
      (node (ref "U8") (pin "17") (pinfunction "GND_17") (pintype "power_in"))
      (node (ref "U8") (pin "3") (pinfunction "GND_3") (pintype "power_in"))
      (node (ref "X1") (pin "2") (pinfunction "NC_2") (pintype "power_in"))
      (node (ref "X1") (pin "4") (pinfunction "NC_4") (pintype "power_in"))
    )
    (net (code "47") (name "Net-(ANT1-Feed_point)") (class "Default")
      (node (ref "ANT1") (pin "2-3") (pinfunction "NC_2-3") (pintype "passive"))
      (node (ref "ANT1") (pin "4") (pinfunction "Feed_point_4") (pintype "input"))
      (node (ref "ANT1") (pin "5-6") (pinfunction "NC_5-6") (pintype "passive"))
      (node (ref "L3") (pin "1") (pinfunction "1_1") (pintype "passive"))
      (node (ref "R11") (pin "2") (pinfunction "2_2") (pintype "passive"))
    )
    (net (code "48") (name "Net-(ANT1-R.E.)") (class "Default")
      (node (ref "ANT1") (pin "1") (pinfunction "R.E._1") (pintype "passive"))
      (node (ref "C16") (pin "2") (pinfunction "2_2") (pintype "passive"))
      (node (ref "C17") (pin "2") (pinfunction "2_2") (pintype "passive"))
    )
    (net (code "49") (name "Net-(B1-CE)") (class "Default")
      (node (ref "B1") (pin "3") (pinfunction "CE_3") (pintype "passive"))
      (node (ref "R20") (pin "2") (pinfunction "2_2") (pintype "passive"))
      (node (ref "R23") (pin "1") (pinfunction "1_1") (pintype "passive"))
      (node (ref "U6") (pin "1") (pinfunction "OUT_1") (pintype "output"))
    )
    (net (code "50") (name "Net-(B1-VIN)") (class "Default")
      (node (ref "B1") (pin "1") (pinfunction "VIN_1") (pintype "passive"))
      (node (ref "C15") (pin "2") (pinfunction "2_2") (pintype "passive"))
      (node (ref "R17") (pin "2") (pinfunction "2_2") (pintype "passive"))
      (node (ref "R18") (pin "2") (pinfunction "2_2") (pintype "passive"))
      (node (ref "U4") (pin "4") (pinfunction "VIN-_4") (pintype "power_in"))
    )
    (net (code "51") (name "Net-(C3-Pad1)") (class "Default")
      (node (ref "C3") (pin "1") (pinfunction "1_1") (pintype "passive"))
      (node (ref "R10") (pin "2") (pinfunction "2_2") (pintype "passive"))
    )
    (net (code "52") (name "Net-(C13-Pad2)") (class "Default")
      (node (ref "C13") (pin "2") (pinfunction "2_2") (pintype "passive"))
      (node (ref "L1") (pin "2") (pinfunction "2_2") (pintype "passive"))
      (node (ref "L2") (pin "1") (pinfunction "1_1") (pintype "passive"))
    )
    (net (code "53") (name "Net-(C14-Pad2)") (class "Default")
      (node (ref "C14") (pin "2") (pinfunction "2_2") (pintype "passive"))
      (node (ref "L2") (pin "2") (pinfunction "2_2") (pintype "passive"))
      (node (ref "R11") (pin "1") (pinfunction "1_1") (pintype "passive"))
    )
    (net (code "54") (name "Net-(D1-A)") (class "Default")
      (node (ref "D1") (pin "2") (pinfunction "A_2") (pintype "passive"))
      (node (ref "R8") (pin "1") (pinfunction "1_1") (pintype "passive"))
    )
    (net (code "55") (name "Net-(D2-A)") (class "Default")
      (node (ref "D2") (pin "2") (pinfunction "A_2") (pintype "passive"))
      (node (ref "R9") (pin "1") (pinfunction "1_1") (pintype "passive"))
    )
    (net (code "56") (name "Net-(J3-CC1)") (class "Default")
      (node (ref "J3") (pin "A5") (pinfunction "CC1_A5") (pintype "bidirectional"))
      (node (ref "R13") (pin "1") (pinfunction "1_1") (pintype "passive"))
    )
    (net (code "57") (name "Net-(J3-CC2)") (class "Default")
      (node (ref "J3") (pin "B5") (pinfunction "CC2_B5") (pintype "bidirectional"))
      (node (ref "R14") (pin "1") (pinfunction "1_1") (pintype "passive"))
    )
    (net (code "58") (name "Net-(L4-Pad2)") (class "Default")
      (node (ref "L4") (pin "2") (pinfunction "2_2") (pintype "passive"))
      (node (ref "L5") (pin "1") (pinfunction "1_1") (pintype "passive"))
    )
    (net (code "59") (name "Net-(R2-Pad1)") (class "Default")
      (node (ref "R2") (pin "1") (pinfunction "1_1") (pintype "passive"))
      (node (ref "U1") (pin "8") (pinfunction "RG_8") (pintype "input"))
    )
    (net (code "60") (name "Net-(R2-Pad2)") (class "Default")
      (node (ref "R2") (pin "2") (pinfunction "2_2") (pintype "passive"))
      (node (ref "U1") (pin "1") (pinfunction "RG_1") (pintype "input"))
    )
    (net (code "61") (name "Net-(R19-Pad2)") (class "Default")
      (node (ref "R19") (pin "2") (pinfunction "2_2") (pintype "passive"))
      (node (ref "R21") (pin "1") (pinfunction "1_1") (pintype "passive"))
      (node (ref "R22") (pin "1") (pinfunction "1_1") (pintype "passive"))
    )
    (net (code "62") (name "Net-(U1-REF)") (class "Default")
      (node (ref "U1") (pin "5") (pinfunction "REF_5") (pintype "input"))
      (node (ref "U2") (pin "3") (pinfunction "-IN_3") (pintype "tri_state"))
      (node (ref "U2") (pin "4") (pinfunction "OUT_4") (pintype "output"))
    )
    (net (code "63") (name "Net-(U2-+IN)") (class "Default")
      (node (ref "R1") (pin "2") (pinfunction "2_2") (pintype "passive"))
      (node (ref "R6") (pin "1") (pinfunction "1_1") (pintype "passive"))
      (node (ref "U2") (pin "1") (pinfunction "+IN_1") (pintype "tri_state"))
    )
    (net (code "64") (name "Net-(U4-OUT)") (class "Default")
      (node (ref "R16") (pin "2") (pinfunction "2_2") (pintype "passive"))
      (node (ref "U4") (pin "1") (pinfunction "OUT_1") (pintype "output"))
    )
    (net (code "65") (name "Net-(U4-V+)") (class "Default")
      (node (ref "R15") (pin "2") (pinfunction "2_2") (pintype "passive"))
      (node (ref "U4") (pin "5") (pinfunction "V+_5") (pintype "power_in"))
    )
    (net (code "66") (name "Net-(U5-DCC)") (class "Default")
      (node (ref "L5") (pin "2") (pinfunction "2_2") (pintype "passive"))
      (node (ref "U5") (pin "47") (pinfunction "DCC_47") (pintype "output"))
    )
    (net (code "67") (name "Net-(U6-VIN+)") (class "Default")
      (node (ref "R20") (pin "1") (pinfunction "1_1") (pintype "passive"))
      (node (ref "R21") (pin "2") (pinfunction "2_2") (pintype "passive"))
      (node (ref "U6") (pin "3") (pinfunction "VIN+_3") (pintype "input"))
    )
    (net (code "68") (name "Net-(U6-VIN-)") (class "Default")
      (node (ref "U6") (pin "4") (pinfunction "VIN-_4") (pintype "input"))
      (node (ref "U6") (pin "5") (pinfunction "VREF_5") (pintype "power_in"))
    )
    (net (code "69") (name "Net-(U7-ISET)") (class "Default")
      (node (ref "R29") (pin "2") (pinfunction "2_2") (pintype "passive"))
      (node (ref "U7") (pin "2") (pinfunction "ISET_2") (pintype "passive"))
    )
    (net (code "70") (name "Net-(U7-STAT)") (class "Default")
      (node (ref "R27") (pin "1") (pinfunction "1_1") (pintype "passive"))
      (node (ref "U7") (pin "5") (pinfunction "STAT_5") (pintype "open_collector"))
    )
    (net (code "71") (name "Net-(U7-TS)") (class "Default")
      (node (ref "R28") (pin "1") (pinfunction "1_1") (pintype "passive"))
      (node (ref "U7") (pin "3") (pinfunction "TS_3") (pintype "passive"))
    )
    (net (code "72") (name "Net-(U7-VSET)") (class "Default")
      (node (ref "R30") (pin "2") (pinfunction "2_2") (pintype "passive"))
      (node (ref "U7") (pin "7") (pinfunction "VSET_7") (pintype "passive"))
    )
    (net (code "73") (name "Net-(U7-~{PG})") (class "Default")
      (node (ref "R26") (pin "1") (pinfunction "1_1") (pintype "passive"))
      (node (ref "U7") (pin "6") (pinfunction "~{PG}_6") (pintype "open_collector"))
    )
    (net (code "74") (name "VBATT") (class "Default")
      (node (ref "C31") (pin "1") (pinfunction "1_1") (pintype "passive"))
      (node (ref "P1") (pin "1") (pinfunction "1_1") (pintype "passive"))
      (node (ref "R17") (pin "1") (pinfunction "1_1") (pintype "passive"))
      (node (ref "R18") (pin "1") (pinfunction "1_1") (pintype "passive"))
      (node (ref "R19") (pin "1") (pinfunction "1_1") (pintype "passive"))
      (node (ref "R24") (pin "2") (pinfunction "2_2") (pintype "passive"))
      (node (ref "R26") (pin "2") (pinfunction "2_2") (pintype "passive"))
      (node (ref "R27") (pin "2") (pinfunction "2_2") (pintype "passive"))
      (node (ref "U4") (pin "3") (pinfunction "VIN+_3") (pintype "power_in"))
      (node (ref "U6") (pin "6") (pinfunction "VDD_6") (pintype "power_in"))
      (node (ref "U7") (pin "8") (pinfunction "OUT_8") (pintype "passive"))
    )
    (net (code "75") (name "VCC") (class "Default")
      (node (ref "B1") (pin "5") (pinfunction "VOUT_5") (pintype "passive"))
      (node (ref "C19") (pin "2") (pinfunction "2_2") (pintype "passive"))
      (node (ref "C2") (pin "2") (pinfunction "2_2") (pintype "passive"))
      (node (ref "C22") (pin "2") (pinfunction "2_2") (pintype "passive"))
      (node (ref "C27") (pin "2") (pinfunction "2_2") (pintype "passive"))
      (node (ref "C29") (pin "2") (pinfunction "2_2") (pintype "passive"))
      (node (ref "C8") (pin "2") (pinfunction "2_2") (pintype "passive"))
      (node (ref "C9") (pin "2") (pinfunction "2_2") (pintype "passive"))
      (node (ref "J1") (pin "1") (pinfunction "3V3_1") (pintype "power_in"))
      (node (ref "R1") (pin "1") (pinfunction "1_1") (pintype "passive"))
      (node (ref "R15") (pin "1") (pinfunction "1_1") (pintype "passive"))
      (node (ref "R5") (pin "1") (pinfunction "1_1") (pintype "passive"))
      (node (ref "R8") (pin "2") (pinfunction "2_2") (pintype "passive"))
      (node (ref "U1") (pin "7") (pinfunction "V+_7") (pintype "power_in"))
      (node (ref "U2") (pin "5") (pinfunction "V+_5") (pintype "power_in"))
      (node (ref "U3") (pin "8") (pinfunction "VDD_8") (pintype "power_in"))
      (node (ref "U5") (pin "12") (pinfunction "VDD_12") (pintype "power_in"))
      (node (ref "U5") (pin "17") (pinfunction "VDD_17") (pintype "power_in"))
      (node (ref "U5") (pin "25") (pinfunction "VDD_25") (pintype "power_in"))
      (node (ref "U5") (pin "37") (pinfunction "VDD_37") (pintype "power_in"))
      (node (ref "U5") (pin "48") (pinfunction "VDD_48") (pintype "power_in"))
    )
    (net (code "76") (name "VCCIO") (class "Default")
      (node (ref "C20") (pin "1") (pinfunction "1_1") (pintype "passive"))
      (node (ref "R31") (pin "1") (pinfunction "1_1") (pintype "passive"))
      (node (ref "R32") (pin "1") (pinfunction "1_1") (pintype "passive"))
      (node (ref "R33") (pin "1") (pinfunction "1_1") (pintype "passive"))
      (node (ref "R34") (pin "1") (pinfunction "1_1") (pintype "passive"))
      (node (ref "U8") (pin "1") (pinfunction "VCCIO_1") (pintype "power_in"))
      (node (ref "U8") (pin "8") (pinfunction "3V3OUT_8") (pintype "power_in"))
      (node (ref "U8") (pin "9") (pinfunction "~{RESET}_9") (pintype "input"))
    )
    (net (code "77") (name "VDDIO") (class "Default")
      (node (ref "C1") (pin "2") (pinfunction "2_2") (pintype "passive"))
      (node (ref "R3") (pin "1") (pinfunction "1_1") (pintype "passive"))
      (node (ref "R4") (pin "1") (pinfunction "1_1") (pintype "passive"))
      (node (ref "U3") (pin "5") (pinfunction "VDDIO_5") (pintype "power_in"))
    )
    (net (code "78") (name "unconnected-(B1-NC-Pad4)") (class "Default")
      (node (ref "B1") (pin "4") (pinfunction "NC_4") (pintype "passive+no_connect"))
    )
    (net (code "79") (name "unconnected-(J3-SBU1-PadA8)") (class "Default")
      (node (ref "J3") (pin "A8") (pinfunction "SBU1_A8") (pintype "bidirectional+no_connect"))
    )
    (net (code "80") (name "unconnected-(J3-SBU2-PadB8)") (class "Default")
      (node (ref "J3") (pin "B8") (pinfunction "SBU2_B8") (pintype "bidirectional+no_connect"))
    )
    (net (code "81") (name "unconnected-(U5-N.C.-Pad28)") (class "Default")
      (node (ref "U5") (pin "28") (pinfunction "N.C._28") (pintype "passive+no_connect"))
    )
    (net (code "82") (name "unconnected-(U8-CBUS0-Pad12)") (class "Default")
      (node (ref "U8") (pin "12") (pinfunction "CBUS0_12") (pintype "bidirectional+no_connect"))
    )
    (net (code "83") (name "unconnected-(U8-CBUS1-Pad11)") (class "Default")
      (node (ref "U8") (pin "11") (pinfunction "CBUS1_11") (pintype "bidirectional+no_connect"))
    )
    (net (code "84") (name "unconnected-(U8-CBUS2-Pad5)") (class "Default")
      (node (ref "U8") (pin "5") (pinfunction "CBUS2_5") (pintype "bidirectional+no_connect"))
    )
    (net (code "85") (name "unconnected-(U8-CBUS3-Pad14)") (class "Default")
      (node (ref "U8") (pin "14") (pinfunction "CBUS3_14") (pintype "bidirectional+no_connect"))
    )
  )
)
